# Sheet1AD9116.net
KiCad netlist of a schematic drawn in Altium Designer
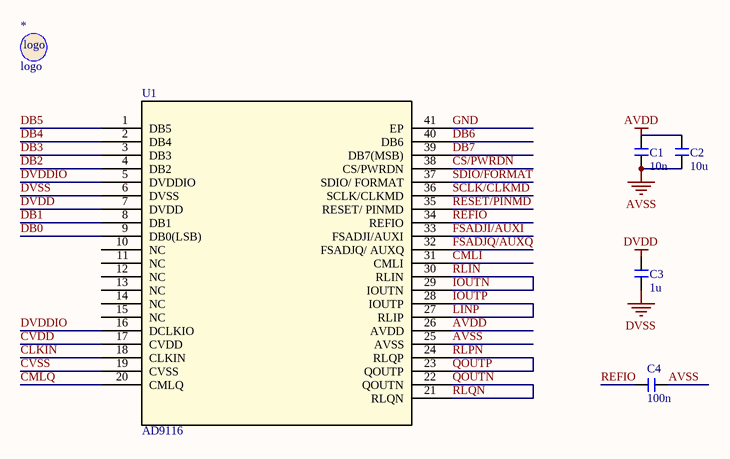
[diagram p0: Sheet1AD9116.SchDoc]

(export (version "E")
  (design (tool "Eeschema 10.0.6"))
  (components
    (comp (ref "*") (value "logo") (footprint "HuajingDevices") (libsource (lib "IL") (part "logo")))
    (comp (ref "C1")
      (value "10n")
      (footprint "C 0603_L")
      (description "无极性贴片电容")
      (fields (field (name "版权归属") "源创客"))
      (libsource (lib "IL") (part "C"))
    )
    (comp (ref "C2")
      (value "10u")
      (footprint "C 0603_L")
      (description "无极性贴片电容")
      (fields (field (name "版权归属") "源创客"))
      (libsource (lib "IL") (part "C"))
    )
    (comp (ref "C3")
      (value "1u")
      (footprint "C 0603_L")
      (description "无极性贴片电容")
      (fields (field (name "版权归属") "源创客"))
      (libsource (lib "IL") (part "C"))
    )
    (comp (ref "C4")
      (value "100n")
      (footprint "C 0603_L")
      (description "无极性贴片电容")
      (fields (field (name "版权归属") "源创客"))
      (libsource (lib "IL") (part "C"))
    )
    (comp (ref "U1")
      (value "AD9116")
      (footprint "CP_40_1_ADI")
      (description "No Description Available")
      (fields
        (field (name "MANUFACTURER_PART_NUMBER") "AD9116BCPZ")
        (field (name "COPYRIGHT") "Copyright (C) 2022 Ultra Librarian. All rights reserved.")
      )
      (libsource (lib "AD9116BCPZ") (part "AD9116BCPZ"))
    )
  )
  (nets
    (net (code "1") (name "/CLKIN") (class "Default")
      (node (ref "U1") (pin "18") (pinfunction "CLKIN_18") (pintype "passive"))
    )
    (net (code "2") (name "/CMLI") (class "Default")
      (node (ref "U1") (pin "31") (pinfunction "CMLI_31") (pintype "passive"))
    )
    (net (code "3") (name "/CMLQ") (class "Default")
      (node (ref "U1") (pin "20") (pinfunction "CMLQ_20") (pintype "passive"))
    )
    (net (code "4") (name "/CS{slash}PWRDN") (class "Default")
      (node (ref "U1") (pin "38") (pinfunction "CS/PWRDN_38") (pintype "passive"))
    )
    (net (code "5") (name "/CVDD") (class "Default")
      (node (ref "U1") (pin "17") (pinfunction "CVDD_17") (pintype "power_in"))
    )
    (net (code "6") (name "/CVSS") (class "Default")
      (node (ref "U1") (pin "19") (pinfunction "CVSS_19") (pintype "power_in"))
    )
    (net (code "7") (name "/DB0") (class "Default")
      (node (ref "U1") (pin "9") (pinfunction "DB0(LSB)_9") (pintype "passive"))
    )
    (net (code "8") (name "/DB1") (class "Default")
      (node (ref "U1") (pin "8") (pinfunction "DB1_8") (pintype "passive"))
    )
    (net (code "9") (name "/DB2") (class "Default")
      (node (ref "U1") (pin "4") (pinfunction "DB2_4") (pintype "passive"))
    )
    (net (code "10") (name "/DB3") (class "Default")
      (node (ref "U1") (pin "3") (pinfunction "DB3_3") (pintype "passive"))
    )
    (net (code "11") (name "/DB4") (class "Default")
      (node (ref "U1") (pin "2") (pinfunction "DB4_2") (pintype "passive"))
    )
    (net (code "12") (name "/DB5") (class "Default")
      (node (ref "U1") (pin "1") (pinfunction "DB5_1") (pintype "passive"))
    )
    (net (code "13") (name "/DB6") (class "Default")
      (node (ref "U1") (pin "40") (pinfunction "DB6_40") (pintype "passive"))
    )
    (net (code "14") (name "/DB7") (class "Default")
      (node (ref "U1") (pin "39") (pinfunction "DB7(MSB)_39") (pintype "passive"))
    )
    (net (code "15") (name "/DVDDIO") (class "Default")
      (node (ref "U1") (pin "16") (pinfunction "DCLKIO_16") (pintype "passive"))
      (node (ref "U1") (pin "5") (pinfunction "DVDDIO_5") (pintype "power_in"))
    )
    (net (code "16") (name "/FSADJI{slash}AUXI") (class "Default")
      (node (ref "U1") (pin "33") (pinfunction "FSADJI/AUXI_33") (pintype "passive"))
    )
    (net (code "17") (name "/FSADJQ{slash}AUXQ") (class "Default")
      (node (ref "U1") (pin "32") (pinfunction "FSADJQ/_AUXQ_32") (pintype "passive"))
    )
    (net (code "18") (name "/GND") (class "Default")
      (node (ref "U1") (pin "41") (pinfunction "EP_41") (pintype "power_in"))
    )
    (net (code "19") (name "/IOUTN") (class "Default")
      (node (ref "U1") (pin "29") (pinfunction "IOUTN_29") (pintype "passive"))
      (node (ref "U1") (pin "30") (pinfunction "RLIN_30") (pintype "passive"))
    )
    (net (code "20") (name "/IOUTP") (class "Default")
      (node (ref "U1") (pin "27") (pinfunction "RLIP_27") (pintype "passive"))
      (node (ref "U1") (pin "28") (pinfunction "IOUTP_28") (pintype "passive"))
    )
    (net (code "21") (name "/QOUTN") (class "Default")
      (node (ref "U1") (pin "21") (pinfunction "RLQN_21") (pintype "passive"))
      (node (ref "U1") (pin "22") (pinfunction "QOUTN_22") (pintype "passive"))
    )
    (net (code "22") (name "/QOUTP") (class "Default")
      (node (ref "U1") (pin "23") (pinfunction "QOUTP_23") (pintype "passive"))
      (node (ref "U1") (pin "24") (pinfunction "RLQP_24") (pintype "passive"))
    )
    (net (code "23") (name "/REFIO") (class "Default")
      (node (ref "C4") (pin "2") (pinfunction "2_2") (pintype "passive"))
      (node (ref "U1") (pin "34") (pinfunction "REFIO_34") (pintype "passive"))
    )
    (net (code "24") (name "/RESET{slash}PINMD") (class "Default")
      (node (ref "U1") (pin "35") (pinfunction "RESET/_PINMD_35") (pintype "passive"))
    )
    (net (code "25") (name "/SCLK{slash}CLKMD") (class "Default")
      (node (ref "U1") (pin "36") (pinfunction "SCLK/CLKMD_36") (pintype "passive"))
    )
    (net (code "26") (name "/SDIO{slash}FORMAT") (class "Default")
      (node (ref "U1") (pin "37") (pinfunction "SDIO/_FORMAT_37") (pintype "passive"))
    )
    (net (code "27") (name "AVDD") (class "Default")
      (node (ref "U1") (pin "26") (pinfunction "AVDD_26") (pintype "power_in"))
    )
    (net (code "28") (name "AVSS") (class "Default")
      (node (ref "C1") (pin "1") (pinfunction "1_1") (pintype "passive"))
      (node (ref "C2") (pin "1") (pinfunction "1_1") (pintype "passive"))
      (node (ref "C4") (pin "1") (pinfunction "1_1") (pintype "passive"))
      (node (ref "U1") (pin "25") (pinfunction "AVSS_25") (pintype "passive"))
    )
    (net (code "29") (name "DVDD") (class "Default")
      (node (ref "U1") (pin "7") (pinfunction "DVDD_7") (pintype "power_in"))
    )
    (net (code "30") (name "DVSS") (class "Default")
      (node (ref "C3") (pin "1") (pinfunction "1_1") (pintype "passive"))
      (node (ref "U1") (pin "6") (pinfunction "DVSS_6") (pintype "power_in"))
    )
    (net (code "31") (name "Net-(C1-Pad2)") (class "Default")
      (node (ref "C1") (pin "2") (pinfunction "2_2") (pintype "passive"))
      (node (ref "C2") (pin "2") (pinfunction "2_2") (pintype "passive"))
    )
    (net (code "32") (name "unconnected-(C3-Pad2)") (class "Default")
      (node (ref "C3") (pin "2") (pinfunction "2_2") (pintype "passive"))
    )
    (net (code "33") (name "unconnected-(U1-NC-Pad10)") (class "Default")
      (node (ref "U1") (pin "10") (pinfunction "NC_10") (pintype "passive"))
    )
    (net (code "34") (name "unconnected-(U1-NC-Pad11)") (class "Default")
      (node (ref "U1") (pin "11") (pinfunction "NC_11") (pintype "passive"))
    )
    (net (code "35") (name "unconnected-(U1-NC-Pad12)") (class "Default")
      (node (ref "U1") (pin "12") (pinfunction "NC_12") (pintype "passive"))
    )
    (net (code "36") (name "unconnected-(U1-NC-Pad13)") (class "Default")
      (node (ref "U1") (pin "13") (pinfunction "NC_13") (pintype "passive"))
    )
    (net (code "37") (name "unconnected-(U1-NC-Pad14)") (class "Default")
      (node (ref "U1") (pin "14") (pinfunction "NC_14") (pintype "passive"))
    )
    (net (code "38") (name "unconnected-(U1-NC-Pad15)") (class "Default")
      (node (ref "U1") (pin "15") (pinfunction "NC_15") (pintype "passive"))
    )
  )
)
